# schematic.net
KiCad netlist of a schematic drawn in EAGLE
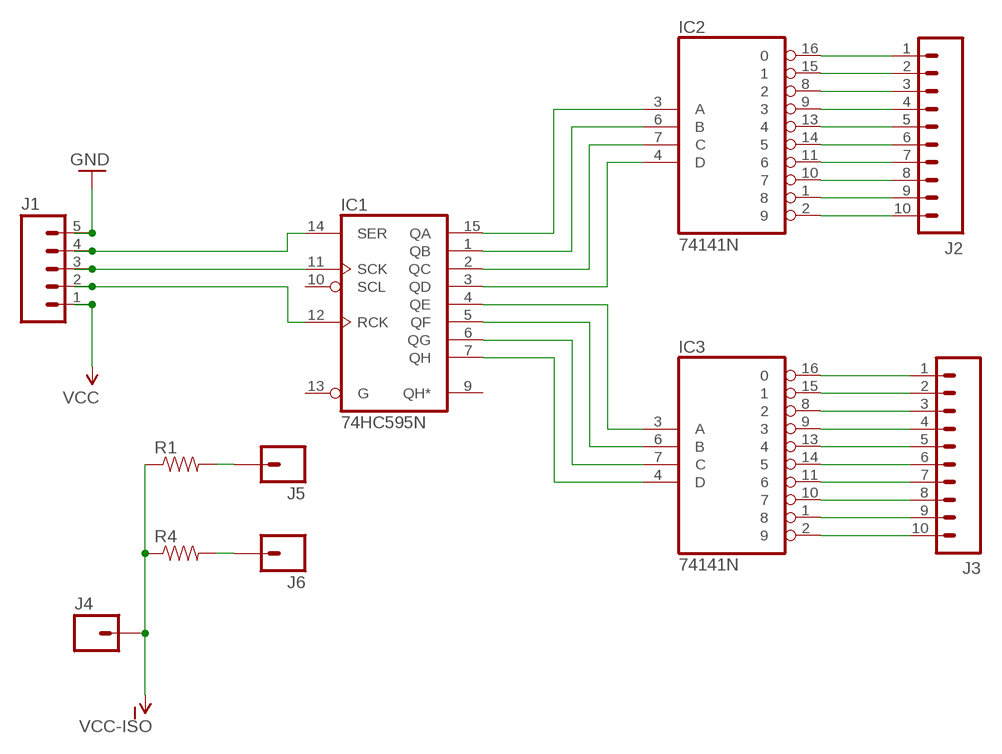
[diagram p0: schematic, sheet 1]

(export (version "E")
  (design (tool "Eeschema 10.0.6"))
  (components
    (comp (ref "IC1")
      (value "74HC595N")
      (footprint "eagle-import:DIL16")
      (libsource (lib "eagle-import") (part "74595NHC"))
    )
    (comp (ref "IC2")
      (value "74141N")
      (footprint "eagle-import:DIL16")
      (libsource (lib "eagle-import") (part "74141N"))
    )
    (comp (ref "IC3")
      (value "74141N")
      (footprint "eagle-import:DIL16")
      (libsource (lib "eagle-import") (part "74141N"))
    )
    (comp (ref "J1")
      (value "M05LOCK")
      (footprint "eagle-import:1X05_LOCK")
      (libsource (lib "eagle-import") (part "M05LOCK"))
    )
    (comp (ref "J2")
      (value "M10LOCK")
      (footprint "eagle-import:1X10_LOCK")
      (libsource (lib "eagle-import") (part "M10LOCK"))
    )
    (comp (ref "J3")
      (value "M10LOCK")
      (footprint "eagle-import:1X10_LOCK")
      (libsource (lib "eagle-import") (part "M10LOCK"))
    )
    (comp (ref "J4")
      (value "M01PTH")
      (footprint "eagle-import:1X01")
      (libsource (lib "eagle-import") (part "M01PTH"))
    )
    (comp (ref "J5")
      (value "M01PTH")
      (footprint "eagle-import:1X01")
      (libsource (lib "eagle-import") (part "M01PTH"))
    )
    (comp (ref "J6")
      (value "M01PTH")
      (footprint "eagle-import:1X01")
      (libsource (lib "eagle-import") (part "M01PTH"))
    )
    (comp (ref "R1")
      (value "RESISTORPTH-1/4W")
      (footprint "eagle-import:AXIAL-0.4")
      (libsource (lib "eagle-import") (part "RESISTORPTH-1/4W"))
    )
    (comp (ref "R4")
      (value "RESISTORPTH-1/4W")
      (footprint "eagle-import:AXIAL-0.4")
      (libsource (lib "eagle-import") (part "RESISTORPTH-1/4W"))
    )
  )
  (nets
    (net (code "1") (name "GND") (class "Default")
      (node (ref "J1") (pin "5") (pinfunction "5_5") (pintype "passive"))
    )
    (net (code "2") (name "Net-(IC1A-QA)") (class "Default")
      (node (ref "IC1") (pin "15") (pinfunction "QA_15") (pintype "tri_state"))
      (node (ref "IC2") (pin "3") (pinfunction "A_3") (pintype "input"))
    )
    (net (code "3") (name "Net-(IC1A-QB)") (class "Default")
      (node (ref "IC1") (pin "1") (pinfunction "QB_1") (pintype "tri_state"))
      (node (ref "IC2") (pin "6") (pinfunction "B_6") (pintype "input"))
    )
    (net (code "4") (name "Net-(IC1A-QC)") (class "Default")
      (node (ref "IC1") (pin "2") (pinfunction "QC_2") (pintype "tri_state"))
      (node (ref "IC2") (pin "7") (pinfunction "C_7") (pintype "input"))
    )
    (net (code "5") (name "Net-(IC1A-QD)") (class "Default")
      (node (ref "IC1") (pin "3") (pinfunction "QD_3") (pintype "tri_state"))
      (node (ref "IC2") (pin "4") (pinfunction "D_4") (pintype "input"))
    )
    (net (code "6") (name "Net-(IC1A-QE)") (class "Default")
      (node (ref "IC1") (pin "4") (pinfunction "QE_4") (pintype "tri_state"))
      (node (ref "IC3") (pin "3") (pinfunction "A_3") (pintype "input"))
    )
    (net (code "7") (name "Net-(IC1A-QF)") (class "Default")
      (node (ref "IC1") (pin "5") (pinfunction "QF_5") (pintype "tri_state"))
      (node (ref "IC3") (pin "6") (pinfunction "B_6") (pintype "input"))
    )
    (net (code "8") (name "Net-(IC1A-QG)") (class "Default")
      (node (ref "IC1") (pin "6") (pinfunction "QG_6") (pintype "tri_state"))
      (node (ref "IC3") (pin "7") (pinfunction "C_7") (pintype "input"))
    )
    (net (code "9") (name "Net-(IC1A-QH)") (class "Default")
      (node (ref "IC1") (pin "7") (pinfunction "QH_7") (pintype "tri_state"))
      (node (ref "IC3") (pin "4") (pinfunction "D_4") (pintype "input"))
    )
    (net (code "10") (name "Net-(IC1A-RCK)") (class "Default")
      (node (ref "IC1") (pin "12") (pinfunction "RCK_12") (pintype "input"))
      (node (ref "J1") (pin "2") (pinfunction "2_2") (pintype "passive"))
    )
    (net (code "11") (name "Net-(IC1A-SCK)") (class "Default")
      (node (ref "IC1") (pin "11") (pinfunction "SCK_11") (pintype "input"))
      (node (ref "J1") (pin "3") (pinfunction "3_3") (pintype "passive"))
    )
    (net (code "12") (name "Net-(IC1A-SER)") (class "Default")
      (node (ref "IC1") (pin "14") (pinfunction "SER_14") (pintype "input"))
      (node (ref "J1") (pin "4") (pinfunction "4_4") (pintype "passive"))
    )
    (net (code "13") (name "Net-(IC2A-0)") (class "Default")
      (node (ref "IC2") (pin "16") (pinfunction "0_16") (pintype "open_collector"))
      (node (ref "J2") (pin "1") (pinfunction "1_1") (pintype "passive"))
    )
    (net (code "14") (name "Net-(IC2A-1)") (class "Default")
      (node (ref "IC2") (pin "15") (pinfunction "1_15") (pintype "open_collector"))
      (node (ref "J2") (pin "2") (pinfunction "2_2") (pintype "passive"))
    )
    (net (code "15") (name "Net-(IC2A-2)") (class "Default")
      (node (ref "IC2") (pin "8") (pinfunction "2_8") (pintype "open_collector"))
      (node (ref "J2") (pin "3") (pinfunction "3_3") (pintype "passive"))
    )
    (net (code "16") (name "Net-(IC2A-3)") (class "Default")
      (node (ref "IC2") (pin "9") (pinfunction "3_9") (pintype "open_collector"))
      (node (ref "J2") (pin "4") (pinfunction "4_4") (pintype "passive"))
    )
    (net (code "17") (name "Net-(IC2A-4)") (class "Default")
      (node (ref "IC2") (pin "13") (pinfunction "4_13") (pintype "open_collector"))
      (node (ref "J2") (pin "5") (pinfunction "5_5") (pintype "passive"))
    )
    (net (code "18") (name "Net-(IC2A-5)") (class "Default")
      (node (ref "IC2") (pin "14") (pinfunction "5_14") (pintype "open_collector"))
      (node (ref "J2") (pin "6") (pinfunction "6_6") (pintype "passive"))
    )
    (net (code "19") (name "Net-(IC2A-6)") (class "Default")
      (node (ref "IC2") (pin "11") (pinfunction "6_11") (pintype "open_collector"))
      (node (ref "J2") (pin "7") (pinfunction "7_7") (pintype "passive"))
    )
    (net (code "20") (name "Net-(IC2A-7)") (class "Default")
      (node (ref "IC2") (pin "10") (pinfunction "7_10") (pintype "open_collector"))
      (node (ref "J2") (pin "8") (pinfunction "8_8") (pintype "passive"))
    )
    (net (code "21") (name "Net-(IC2A-8)") (class "Default")
      (node (ref "IC2") (pin "1") (pinfunction "8_1") (pintype "open_collector"))
      (node (ref "J2") (pin "9") (pinfunction "9_9") (pintype "passive"))
    )
    (net (code "22") (name "Net-(IC2A-9)") (class "Default")
      (node (ref "IC2") (pin "2") (pinfunction "9_2") (pintype "open_collector"))
      (node (ref "J2") (pin "10") (pinfunction "10_10") (pintype "passive"))
    )
    (net (code "23") (name "Net-(IC3A-0)") (class "Default")
      (node (ref "IC3") (pin "16") (pinfunction "0_16") (pintype "open_collector"))
      (node (ref "J3") (pin "1") (pinfunction "1_1") (pintype "passive"))
    )
    (net (code "24") (name "Net-(IC3A-1)") (class "Default")
      (node (ref "IC3") (pin "15") (pinfunction "1_15") (pintype "open_collector"))
      (node (ref "J3") (pin "2") (pinfunction "2_2") (pintype "passive"))
    )
    (net (code "25") (name "Net-(IC3A-2)") (class "Default")
      (node (ref "IC3") (pin "8") (pinfunction "2_8") (pintype "open_collector"))
      (node (ref "J3") (pin "3") (pinfunction "3_3") (pintype "passive"))
    )
    (net (code "26") (name "Net-(IC3A-3)") (class "Default")
      (node (ref "IC3") (pin "9") (pinfunction "3_9") (pintype "open_collector"))
      (node (ref "J3") (pin "4") (pinfunction "4_4") (pintype "passive"))
    )
    (net (code "27") (name "Net-(IC3A-4)") (class "Default")
      (node (ref "IC3") (pin "13") (pinfunction "4_13") (pintype "open_collector"))
      (node (ref "J3") (pin "5") (pinfunction "5_5") (pintype "passive"))
    )
    (net (code "28") (name "Net-(IC3A-5)") (class "Default")
      (node (ref "IC3") (pin "14") (pinfunction "5_14") (pintype "open_collector"))
      (node (ref "J3") (pin "6") (pinfunction "6_6") (pintype "passive"))
    )
    (net (code "29") (name "Net-(IC3A-6)") (class "Default")
      (node (ref "IC3") (pin "11") (pinfunction "6_11") (pintype "open_collector"))
      (node (ref "J3") (pin "7") (pinfunction "7_7") (pintype "passive"))
    )
    (net (code "30") (name "Net-(IC3A-7)") (class "Default")
      (node (ref "IC3") (pin "10") (pinfunction "7_10") (pintype "open_collector"))
      (node (ref "J3") (pin "8") (pinfunction "8_8") (pintype "passive"))
    )
    (net (code "31") (name "Net-(IC3A-8)") (class "Default")
      (node (ref "IC3") (pin "1") (pinfunction "8_1") (pintype "open_collector"))
      (node (ref "J3") (pin "9") (pinfunction "9_9") (pintype "passive"))
    )
    (net (code "32") (name "Net-(IC3A-9)") (class "Default")
      (node (ref "IC3") (pin "2") (pinfunction "9_2") (pintype "open_collector"))
      (node (ref "J3") (pin "10") (pinfunction "10_10") (pintype "passive"))
    )
    (net (code "33") (name "Net-(R1-2)") (class "Default")
      (node (ref "J5") (pin "1") (pinfunction "1_1") (pintype "passive"))
      (node (ref "R1") (pin "P$2") (pinfunction "2_P$2") (pintype "passive"))
    )
    (net (code "34") (name "Net-(R4-2)") (class "Default")
      (node (ref "J6") (pin "1") (pinfunction "1_1") (pintype "passive"))
      (node (ref "R4") (pin "P$2") (pinfunction "2_P$2") (pintype "passive"))
    )
    (net (code "35") (name "VCC") (class "Default")
      (node (ref "J1") (pin "1") (pinfunction "1_1") (pintype "passive"))
    )
    (net (code "36") (name "VCC-ISO") (class "Default")
      (node (ref "J4") (pin "1") (pinfunction "1_1") (pintype "passive"))
      (node (ref "R1") (pin "P$1") (pinfunction "1_P$1") (pintype "passive"))
      (node (ref "R4") (pin "P$1") (pinfunction "1_P$1") (pintype "passive"))
    )
    (net (code "37") (name "unconnected-(IC1A-G-Pad13)") (class "Default")
      (node (ref "IC1") (pin "13") (pinfunction "G_13") (pintype "input"))
    )
    (net (code "38") (name "unconnected-(IC1A-QH*-Pad9)") (class "Default")
      (node (ref "IC1") (pin "9") (pinfunction "QH*_9") (pintype "tri_state"))
    )
    (net (code "39") (name "unconnected-(IC1A-SCL-Pad10)") (class "Default")
      (node (ref "IC1") (pin "10") (pinfunction "SCL_10") (pintype "input"))
    )
  )
)
